# oresat-backplane-for-0_3.net
KiCad netlist of a schematic drawn in EAGLE
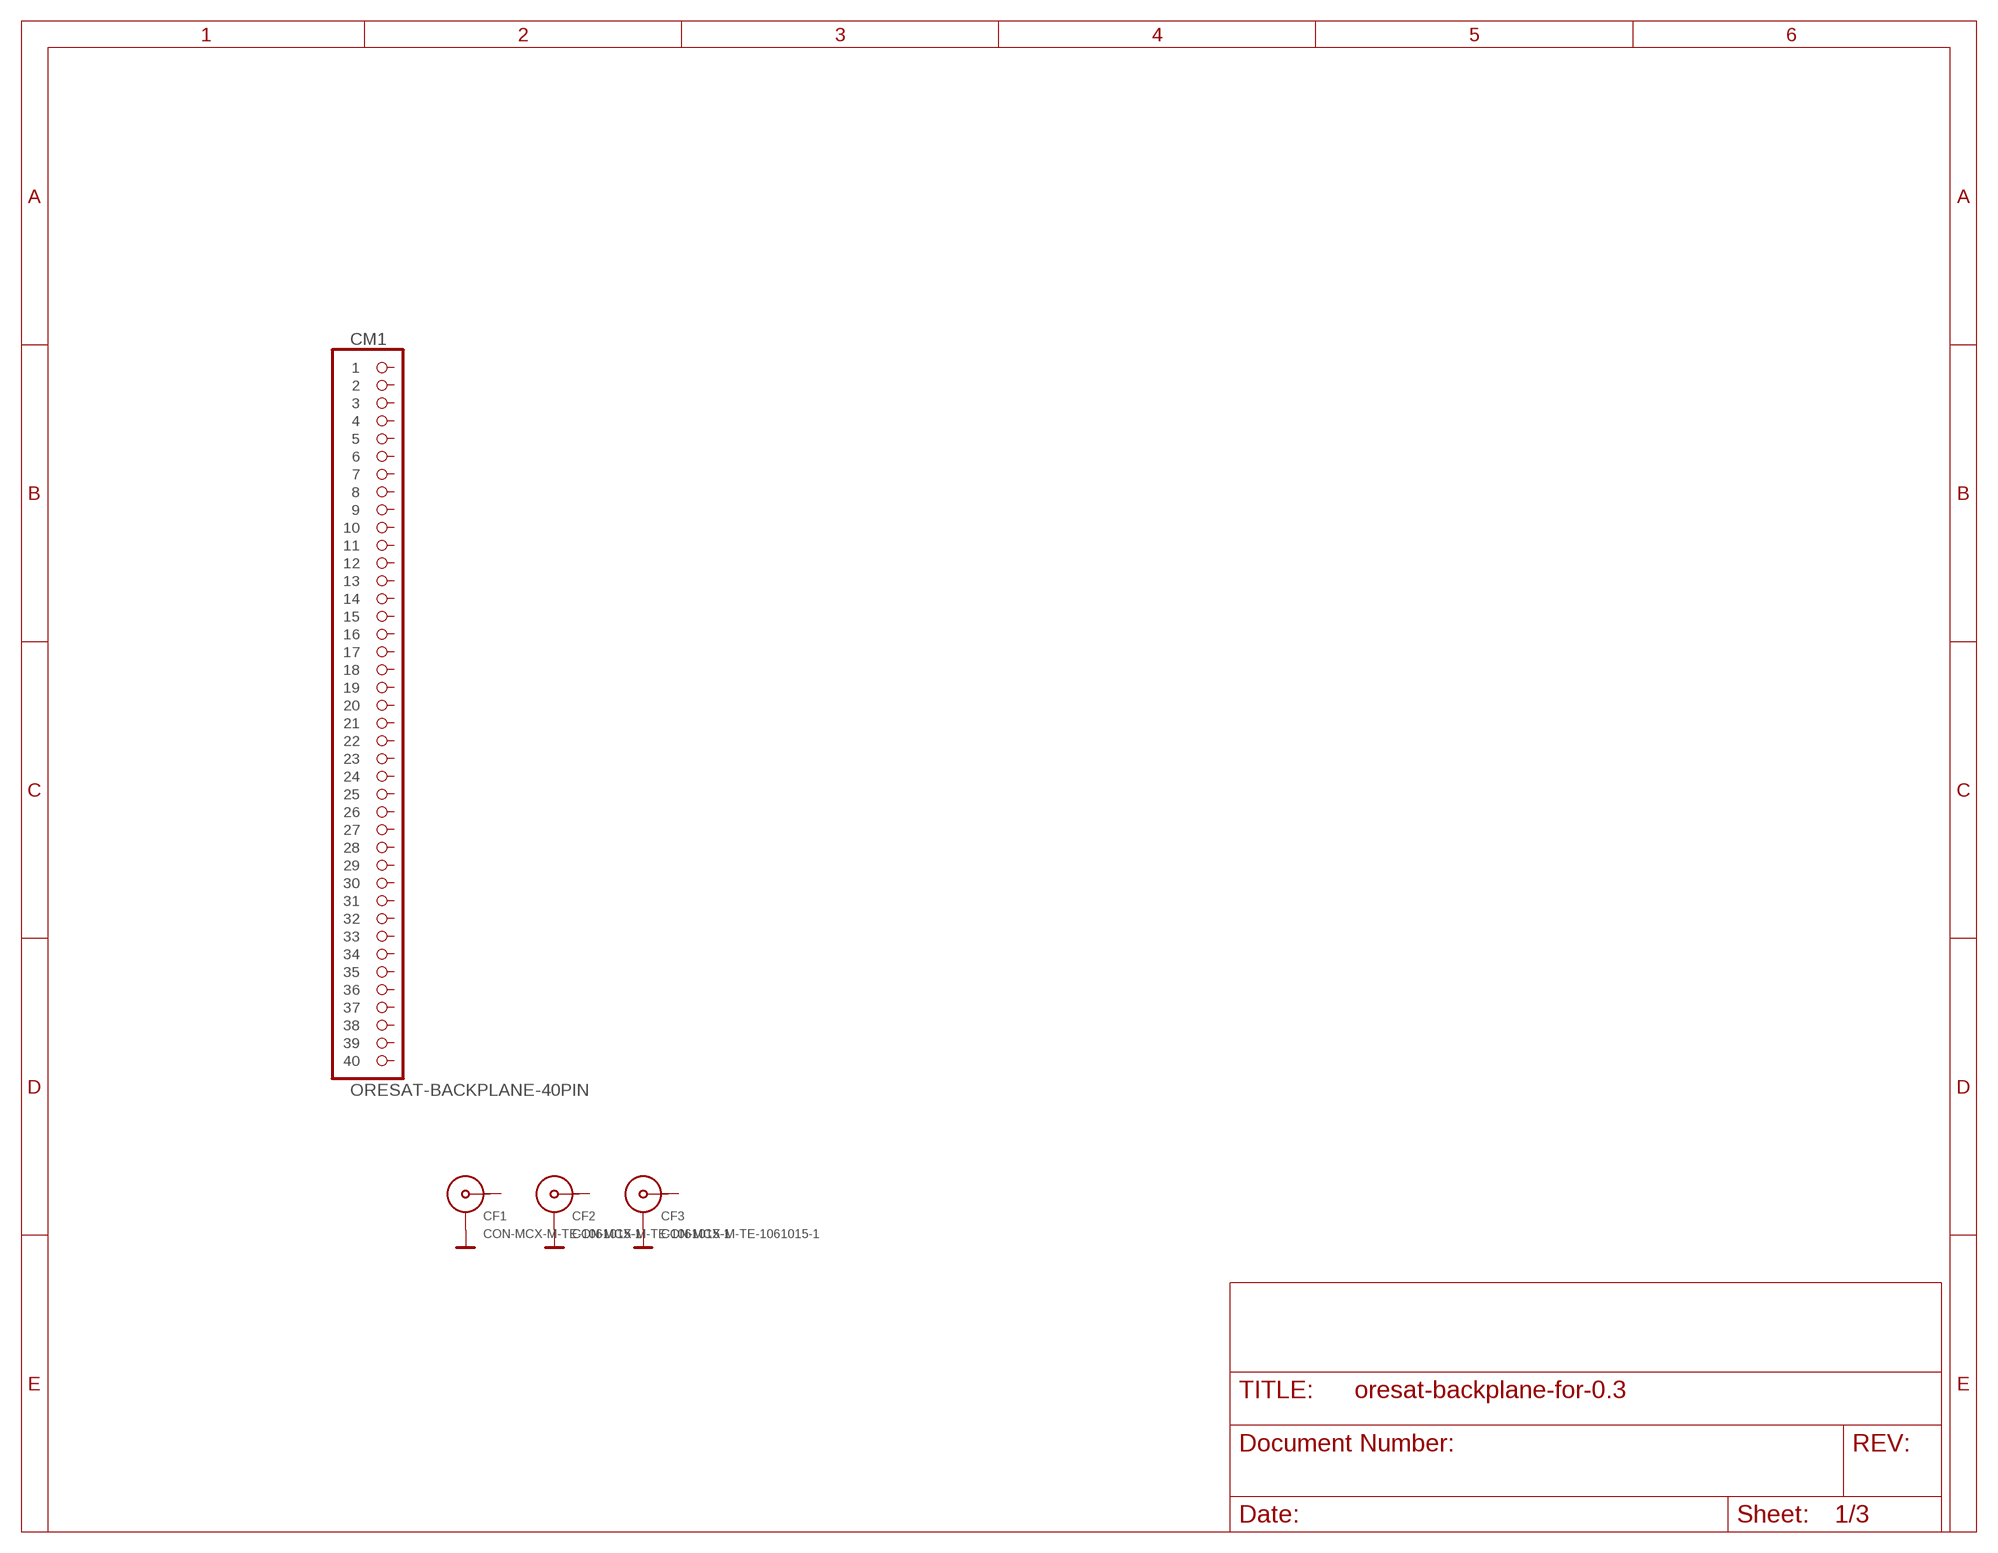
[diagram p0: schematic, sheet 1]
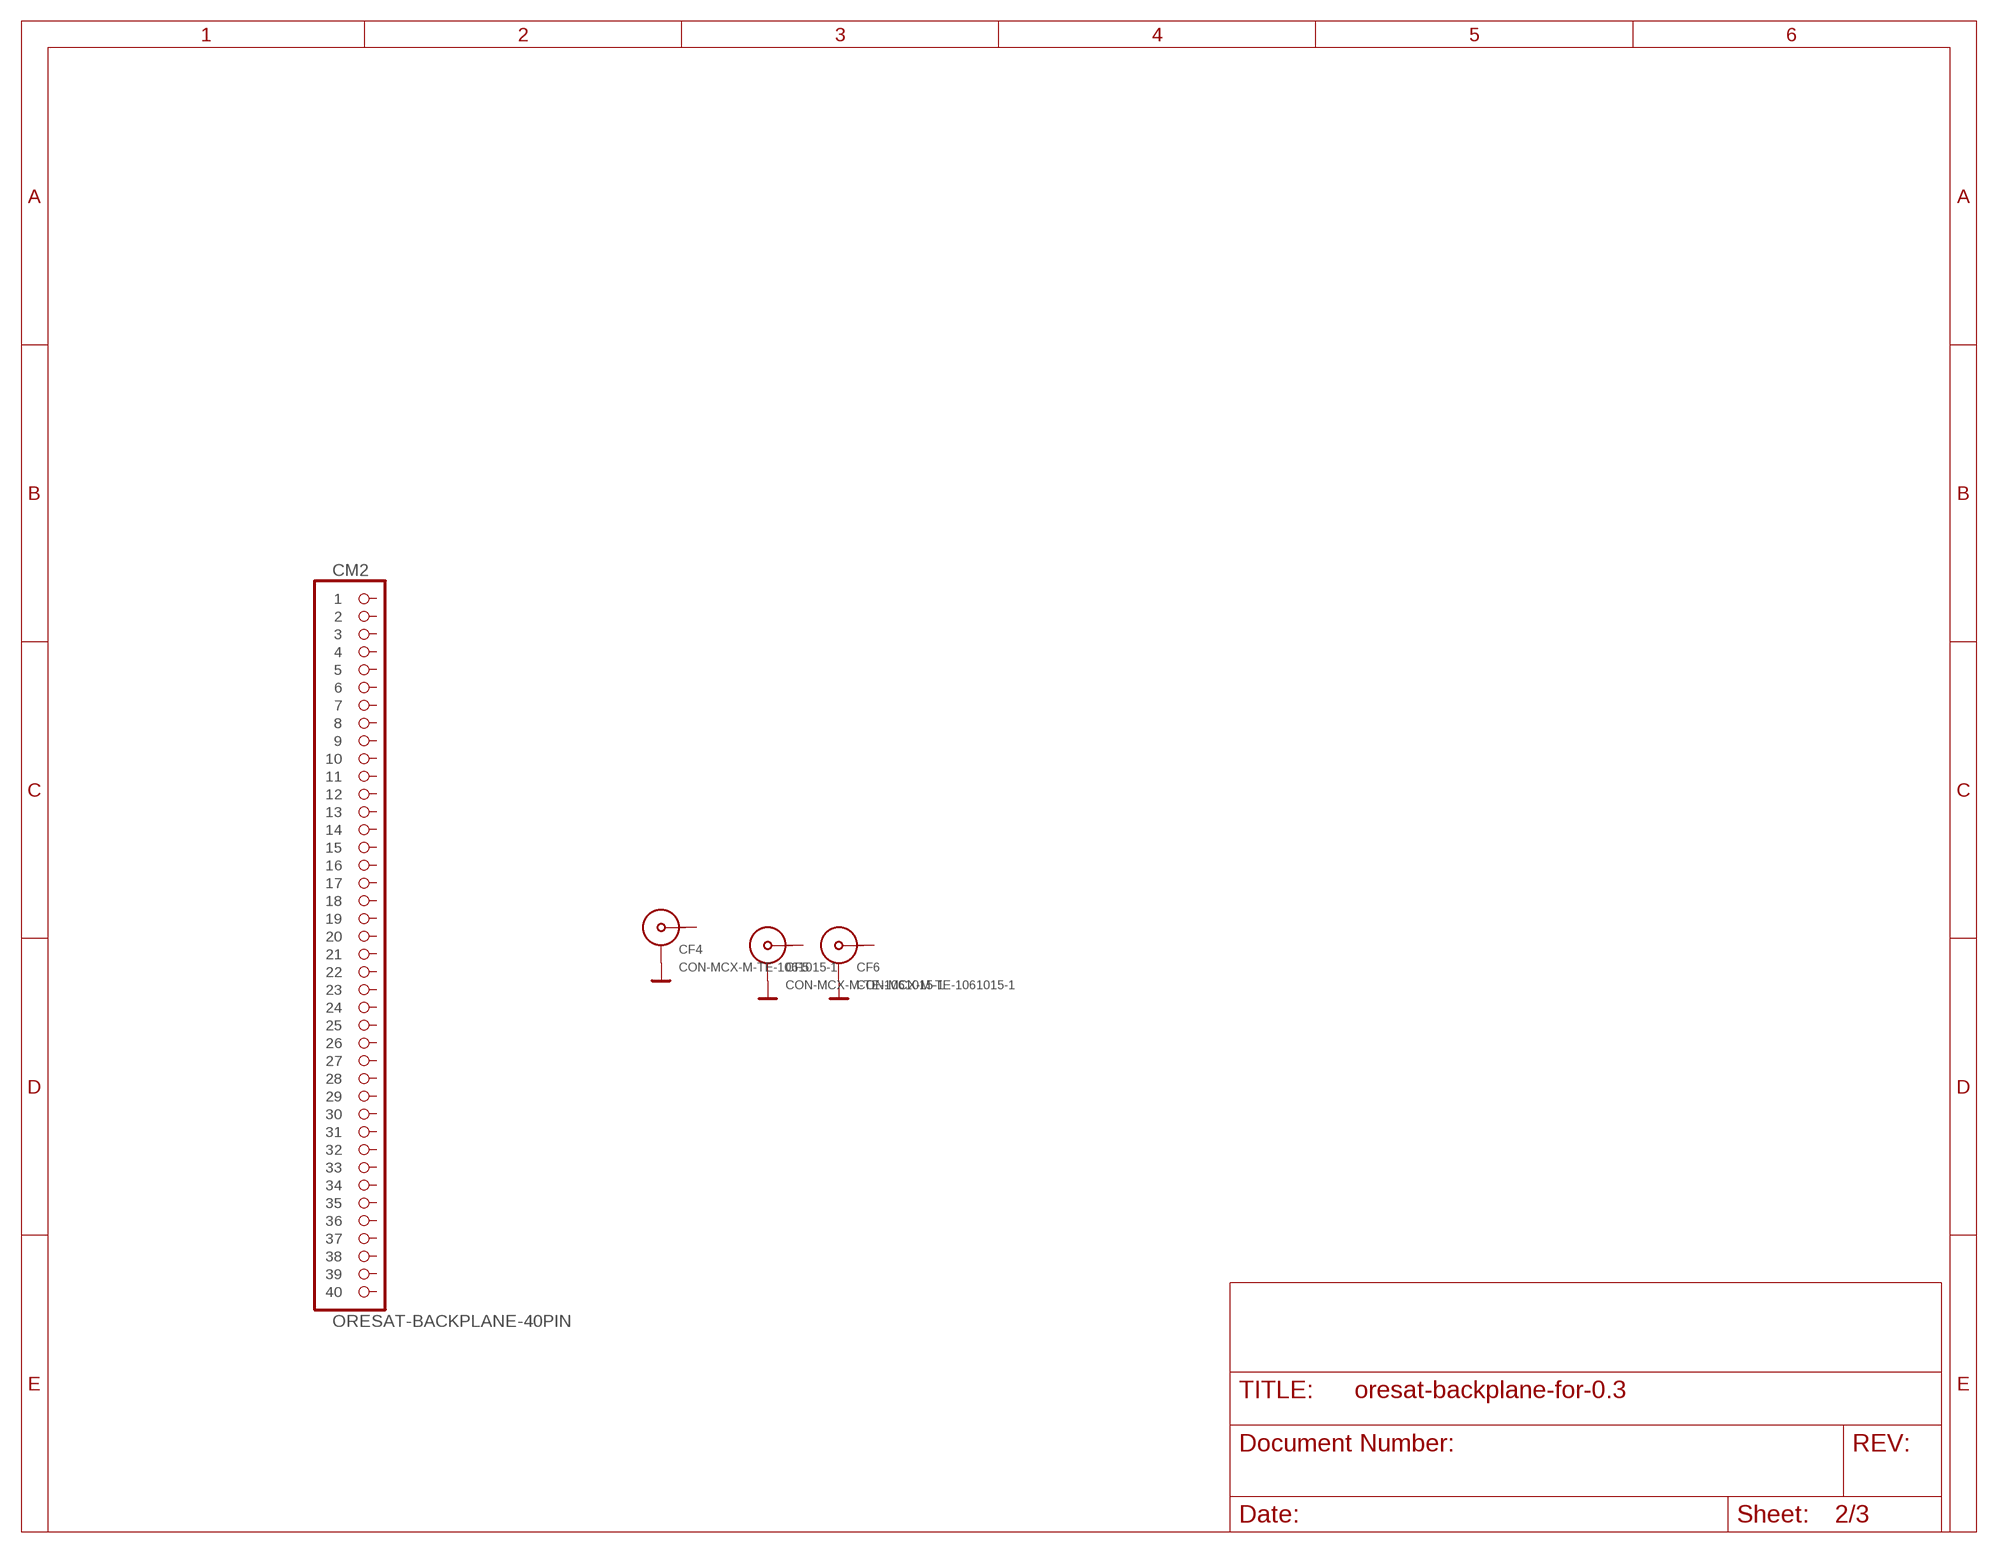
[diagram p1: schematic, sheet 2]
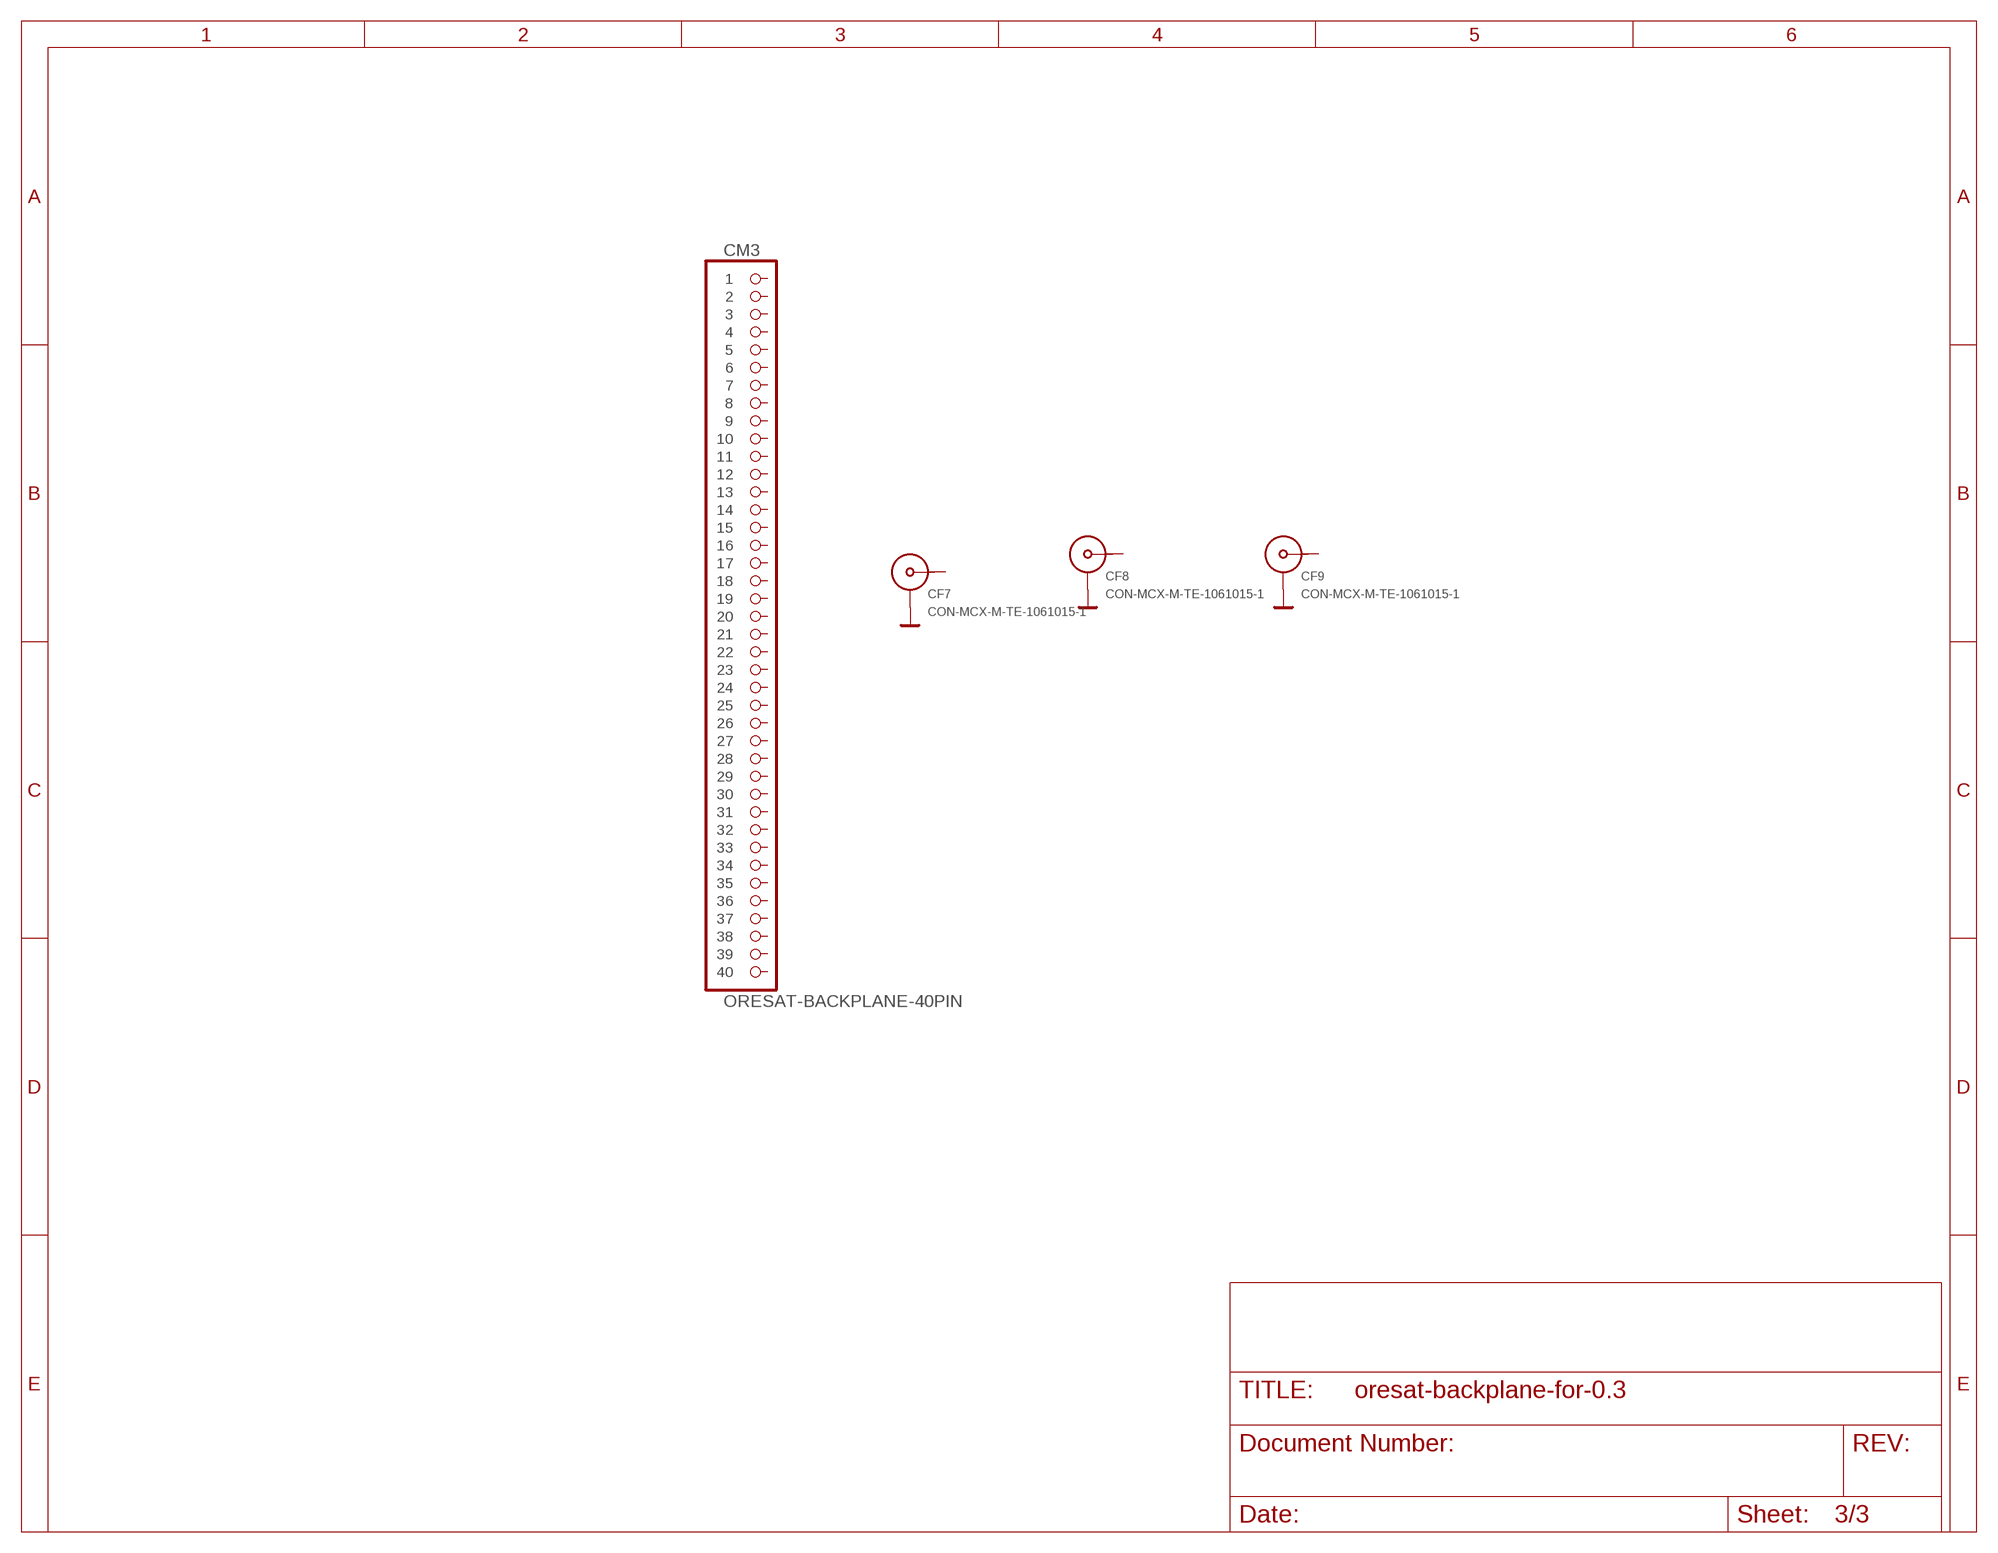
[diagram p2: schematic, sheet 3]

(export (version "E")
  (design (tool "Eeschema 10.0.6"))
  (components
    (comp (ref "CF4")
      (value "CON-MCX-M-TE-1061015-1")
      (footprint "eagle-import:CONN_1061015-1_TYCO")
      (fields
        (field (name "MANUFACTURER_PART_NUMBER") "1061015-1")
        (field (name "RSPARTNUMBER") "7130953")
        (field (name "COPYRIGHT") "Copyright (C) 2015 Accelerated Designs. All rights reserved")
      )
      (libsource (lib "eagle-import") (part "CON-MCX-M-TE-1061015-1"))
    )
    (comp (ref "CF5")
      (value "CON-MCX-M-TE-1061015-1")
      (footprint "eagle-import:CONN_1061015-1_TYCO")
      (fields
        (field (name "MANUFACTURER_PART_NUMBER") "1061015-1")
        (field (name "RSPARTNUMBER") "7130953")
        (field (name "COPYRIGHT") "Copyright (C) 2015 Accelerated Designs. All rights reserved")
      )
      (libsource (lib "eagle-import") (part "CON-MCX-M-TE-1061015-1"))
    )
    (comp (ref "CF6")
      (value "CON-MCX-M-TE-1061015-1")
      (footprint "eagle-import:CONN_1061015-1_TYCO")
      (fields
        (field (name "MANUFACTURER_PART_NUMBER") "1061015-1")
        (field (name "RSPARTNUMBER") "7130953")
        (field (name "COPYRIGHT") "Copyright (C) 2015 Accelerated Designs. All rights reserved")
      )
      (libsource (lib "eagle-import") (part "CON-MCX-M-TE-1061015-1"))
    )
    (comp (ref "CM2")
      (value "ORESAT-BACKPLANE-40PIN")
      (footprint "eagle-import:HARWIN-ARCHER-M50-3502042")
      (libsource (lib "eagle-import") (part "ORESAT-BACKPLANE-40PIN"))
    )
    (comp (ref "CF7")
      (value "CON-MCX-M-TE-1061015-1")
      (footprint "eagle-import:CONN_1061015-1_TYCO")
      (fields
        (field (name "MANUFACTURER_PART_NUMBER") "1061015-1")
        (field (name "RSPARTNUMBER") "7130953")
        (field (name "COPYRIGHT") "Copyright (C) 2015 Accelerated Designs. All rights reserved")
      )
      (libsource (lib "eagle-import") (part "CON-MCX-M-TE-1061015-1"))
    )
    (comp (ref "CF8")
      (value "CON-MCX-M-TE-1061015-1")
      (footprint "eagle-import:CONN_1061015-1_TYCO")
      (fields
        (field (name "MANUFACTURER_PART_NUMBER") "1061015-1")
        (field (name "RSPARTNUMBER") "7130953")
        (field (name "COPYRIGHT") "Copyright (C) 2015 Accelerated Designs. All rights reserved")
      )
      (libsource (lib "eagle-import") (part "CON-MCX-M-TE-1061015-1"))
    )
    (comp (ref "CF9")
      (value "CON-MCX-M-TE-1061015-1")
      (footprint "eagle-import:CONN_1061015-1_TYCO")
      (fields
        (field (name "MANUFACTURER_PART_NUMBER") "1061015-1")
        (field (name "RSPARTNUMBER") "7130953")
        (field (name "COPYRIGHT") "Copyright (C) 2015 Accelerated Designs. All rights reserved")
      )
      (libsource (lib "eagle-import") (part "CON-MCX-M-TE-1061015-1"))
    )
    (comp (ref "CM3")
      (value "ORESAT-BACKPLANE-40PIN")
      (footprint "eagle-import:HARWIN-ARCHER-M50-3502042")
      (libsource (lib "eagle-import") (part "ORESAT-BACKPLANE-40PIN"))
    )
    (comp (ref "CF1")
      (value "CON-MCX-M-TE-1061015-1")
      (footprint "eagle-import:CONN_1061015-1_TYCO")
      (fields
        (field (name "MANUFACTURER_PART_NUMBER") "1061015-1")
        (field (name "RSPARTNUMBER") "7130953")
        (field (name "COPYRIGHT") "Copyright (C) 2015 Accelerated Designs. All rights reserved")
      )
      (libsource (lib "eagle-import") (part "CON-MCX-M-TE-1061015-1"))
    )
    (comp (ref "CF2")
      (value "CON-MCX-M-TE-1061015-1")
      (footprint "eagle-import:CONN_1061015-1_TYCO")
      (fields
        (field (name "MANUFACTURER_PART_NUMBER") "1061015-1")
        (field (name "RSPARTNUMBER") "7130953")
        (field (name "COPYRIGHT") "Copyright (C) 2015 Accelerated Designs. All rights reserved")
      )
      (libsource (lib "eagle-import") (part "CON-MCX-M-TE-1061015-1"))
    )
    (comp (ref "CF3")
      (value "CON-MCX-M-TE-1061015-1")
      (footprint "eagle-import:CONN_1061015-1_TYCO")
      (fields
        (field (name "MANUFACTURER_PART_NUMBER") "1061015-1")
        (field (name "RSPARTNUMBER") "7130953")
        (field (name "COPYRIGHT") "Copyright (C) 2015 Accelerated Designs. All rights reserved")
      )
      (libsource (lib "eagle-import") (part "CON-MCX-M-TE-1061015-1"))
    )
    (comp (ref "CM1")
      (value "ORESAT-BACKPLANE-40PIN")
      (footprint "eagle-import:HARWIN-ARCHER-M50-3502042")
      (libsource (lib "eagle-import") (part "ORESAT-BACKPLANE-40PIN"))
    )
  )
  (nets
    (net (code "1") (name "GND") (class "Default")
      (node (ref "CF1") (pin "SHIELD1") (pinfunction "SHIELD_SHIELD1") (pintype "passive"))
      (node (ref "CF1") (pin "SHIELD2") (pinfunction "SHIELD_SHIELD2") (pintype "passive"))
      (node (ref "CF1") (pin "SHIELD3") (pinfunction "SHIELD_SHIELD3") (pintype "passive"))
      (node (ref "CF1") (pin "SHIELD4") (pinfunction "SHIELD_SHIELD4") (pintype "passive"))
      (node (ref "CF2") (pin "SHIELD1") (pinfunction "SHIELD_SHIELD1") (pintype "passive"))
      (node (ref "CF2") (pin "SHIELD2") (pinfunction "SHIELD_SHIELD2") (pintype "passive"))
      (node (ref "CF2") (pin "SHIELD3") (pinfunction "SHIELD_SHIELD3") (pintype "passive"))
      (node (ref "CF2") (pin "SHIELD4") (pinfunction "SHIELD_SHIELD4") (pintype "passive"))
      (node (ref "CF3") (pin "SHIELD1") (pinfunction "SHIELD_SHIELD1") (pintype "passive"))
      (node (ref "CF3") (pin "SHIELD2") (pinfunction "SHIELD_SHIELD2") (pintype "passive"))
      (node (ref "CF3") (pin "SHIELD3") (pinfunction "SHIELD_SHIELD3") (pintype "passive"))
      (node (ref "CF3") (pin "SHIELD4") (pinfunction "SHIELD_SHIELD4") (pintype "passive"))
      (node (ref "CF4") (pin "SHIELD1") (pinfunction "SHIELD_SHIELD1") (pintype "passive"))
      (node (ref "CF4") (pin "SHIELD2") (pinfunction "SHIELD_SHIELD2") (pintype "passive"))
      (node (ref "CF4") (pin "SHIELD3") (pinfunction "SHIELD_SHIELD3") (pintype "passive"))
      (node (ref "CF4") (pin "SHIELD4") (pinfunction "SHIELD_SHIELD4") (pintype "passive"))
      (node (ref "CF5") (pin "SHIELD1") (pinfunction "SHIELD_SHIELD1") (pintype "passive"))
      (node (ref "CF5") (pin "SHIELD2") (pinfunction "SHIELD_SHIELD2") (pintype "passive"))
      (node (ref "CF5") (pin "SHIELD3") (pinfunction "SHIELD_SHIELD3") (pintype "passive"))
      (node (ref "CF5") (pin "SHIELD4") (pinfunction "SHIELD_SHIELD4") (pintype "passive"))
      (node (ref "CF6") (pin "SHIELD1") (pinfunction "SHIELD_SHIELD1") (pintype "passive"))
      (node (ref "CF6") (pin "SHIELD2") (pinfunction "SHIELD_SHIELD2") (pintype "passive"))
      (node (ref "CF6") (pin "SHIELD3") (pinfunction "SHIELD_SHIELD3") (pintype "passive"))
      (node (ref "CF6") (pin "SHIELD4") (pinfunction "SHIELD_SHIELD4") (pintype "passive"))
      (node (ref "CF7") (pin "SHIELD1") (pinfunction "SHIELD_SHIELD1") (pintype "passive"))
      (node (ref "CF7") (pin "SHIELD2") (pinfunction "SHIELD_SHIELD2") (pintype "passive"))
      (node (ref "CF7") (pin "SHIELD3") (pinfunction "SHIELD_SHIELD3") (pintype "passive"))
      (node (ref "CF7") (pin "SHIELD4") (pinfunction "SHIELD_SHIELD4") (pintype "passive"))
      (node (ref "CF8") (pin "SHIELD1") (pinfunction "SHIELD_SHIELD1") (pintype "passive"))
      (node (ref "CF8") (pin "SHIELD2") (pinfunction "SHIELD_SHIELD2") (pintype "passive"))
      (node (ref "CF8") (pin "SHIELD3") (pinfunction "SHIELD_SHIELD3") (pintype "passive"))
      (node (ref "CF8") (pin "SHIELD4") (pinfunction "SHIELD_SHIELD4") (pintype "passive"))
      (node (ref "CF9") (pin "SHIELD1") (pinfunction "SHIELD_SHIELD1") (pintype "passive"))
      (node (ref "CF9") (pin "SHIELD2") (pinfunction "SHIELD_SHIELD2") (pintype "passive"))
      (node (ref "CF9") (pin "SHIELD3") (pinfunction "SHIELD_SHIELD3") (pintype "passive"))
      (node (ref "CF9") (pin "SHIELD4") (pinfunction "SHIELD_SHIELD4") (pintype "passive"))
    )
    (net (code "2") (name "unconnected-(CF1-PadCENTER)") (class "Default")
      (node (ref "CF1") (pin "CENTER") (pinfunction "CENTER_CENTER") (pintype "passive"))
    )
    (net (code "3") (name "unconnected-(CF2-PadCENTER)") (class "Default")
      (node (ref "CF2") (pin "CENTER") (pinfunction "CENTER_CENTER") (pintype "passive"))
    )
    (net (code "4") (name "unconnected-(CF3-PadCENTER)") (class "Default")
      (node (ref "CF3") (pin "CENTER") (pinfunction "CENTER_CENTER") (pintype "passive"))
    )
    (net (code "5") (name "unconnected-(CF4-PadCENTER)") (class "Default")
      (node (ref "CF4") (pin "CENTER") (pinfunction "CENTER_CENTER") (pintype "passive"))
    )
    (net (code "6") (name "unconnected-(CF5-PadCENTER)") (class "Default")
      (node (ref "CF5") (pin "CENTER") (pinfunction "CENTER_CENTER") (pintype "passive"))
    )
    (net (code "7") (name "unconnected-(CF6-PadCENTER)") (class "Default")
      (node (ref "CF6") (pin "CENTER") (pinfunction "CENTER_CENTER") (pintype "passive"))
    )
    (net (code "8") (name "unconnected-(CF7-PadCENTER)") (class "Default")
      (node (ref "CF7") (pin "CENTER") (pinfunction "CENTER_CENTER") (pintype "passive"))
    )
    (net (code "9") (name "unconnected-(CF8-PadCENTER)") (class "Default")
      (node (ref "CF8") (pin "CENTER") (pinfunction "CENTER_CENTER") (pintype "passive"))
    )
    (net (code "10") (name "unconnected-(CF9-PadCENTER)") (class "Default")
      (node (ref "CF9") (pin "CENTER") (pinfunction "CENTER_CENTER") (pintype "passive"))
    )
    (net (code "11") (name "unconnected-(CM1-1-PadP$1)") (class "Default")
      (node (ref "CM1") (pin "P$1") (pinfunction "1_P$1") (pintype "passive"))
    )
    (net (code "12") (name "unconnected-(CM1-2-PadP$2)") (class "Default")
      (node (ref "CM1") (pin "P$2") (pinfunction "2_P$2") (pintype "passive"))
    )
    (net (code "13") (name "unconnected-(CM1-3-PadP$3)") (class "Default")
      (node (ref "CM1") (pin "P$3") (pinfunction "3_P$3") (pintype "passive"))
    )
    (net (code "14") (name "unconnected-(CM1-4-PadP$4)") (class "Default")
      (node (ref "CM1") (pin "P$4") (pinfunction "4_P$4") (pintype "passive"))
    )
    (net (code "15") (name "unconnected-(CM1-5-PadP$5)") (class "Default")
      (node (ref "CM1") (pin "P$5") (pinfunction "5_P$5") (pintype "passive"))
    )
    (net (code "16") (name "unconnected-(CM1-6-PadP$6)") (class "Default")
      (node (ref "CM1") (pin "P$6") (pinfunction "6_P$6") (pintype "passive"))
    )
    (net (code "17") (name "unconnected-(CM1-7-PadP$7)") (class "Default")
      (node (ref "CM1") (pin "P$7") (pinfunction "7_P$7") (pintype "passive"))
    )
    (net (code "18") (name "unconnected-(CM1-8-PadP$8)") (class "Default")
      (node (ref "CM1") (pin "P$8") (pinfunction "8_P$8") (pintype "passive"))
    )
    (net (code "19") (name "unconnected-(CM1-9-PadP$9)") (class "Default")
      (node (ref "CM1") (pin "P$9") (pinfunction "9_P$9") (pintype "passive"))
    )
    (net (code "20") (name "unconnected-(CM1-10-PadP$10)") (class "Default")
      (node (ref "CM1") (pin "P$10") (pinfunction "10_P$10") (pintype "passive"))
    )
    (net (code "21") (name "unconnected-(CM1-11-PadP$11)") (class "Default")
      (node (ref "CM1") (pin "P$11") (pinfunction "11_P$11") (pintype "passive"))
    )
    (net (code "22") (name "unconnected-(CM1-12-PadP$12)") (class "Default")
      (node (ref "CM1") (pin "P$12") (pinfunction "12_P$12") (pintype "passive"))
    )
    (net (code "23") (name "unconnected-(CM1-13-PadP$13)") (class "Default")
      (node (ref "CM1") (pin "P$13") (pinfunction "13_P$13") (pintype "passive"))
    )
    (net (code "24") (name "unconnected-(CM1-14-PadP$14)") (class "Default")
      (node (ref "CM1") (pin "P$14") (pinfunction "14_P$14") (pintype "passive"))
    )
    (net (code "25") (name "unconnected-(CM1-15-PadP$15)") (class "Default")
      (node (ref "CM1") (pin "P$15") (pinfunction "15_P$15") (pintype "passive"))
    )
    (net (code "26") (name "unconnected-(CM1-16-PadP$16)") (class "Default")
      (node (ref "CM1") (pin "P$16") (pinfunction "16_P$16") (pintype "passive"))
    )
    (net (code "27") (name "unconnected-(CM1-17-PadP$17)") (class "Default")
      (node (ref "CM1") (pin "P$17") (pinfunction "17_P$17") (pintype "passive"))
    )
    (net (code "28") (name "unconnected-(CM1-18-PadP$18)") (class "Default")
      (node (ref "CM1") (pin "P$18") (pinfunction "18_P$18") (pintype "passive"))
    )
    (net (code "29") (name "unconnected-(CM1-19-PadP$19)") (class "Default")
      (node (ref "CM1") (pin "P$19") (pinfunction "19_P$19") (pintype "passive"))
    )
    (net (code "30") (name "unconnected-(CM1-20-PadP$20)") (class "Default")
      (node (ref "CM1") (pin "P$20") (pinfunction "20_P$20") (pintype "passive"))
    )
    (net (code "31") (name "unconnected-(CM1-21-PadP$21)") (class "Default")
      (node (ref "CM1") (pin "P$21") (pinfunction "21_P$21") (pintype "passive"))
    )
    (net (code "32") (name "unconnected-(CM1-22-PadP$22)") (class "Default")
      (node (ref "CM1") (pin "P$22") (pinfunction "22_P$22") (pintype "passive"))
    )
    (net (code "33") (name "unconnected-(CM1-23-PadP$23)") (class "Default")
      (node (ref "CM1") (pin "P$23") (pinfunction "23_P$23") (pintype "passive"))
    )
    (net (code "34") (name "unconnected-(CM1-24-PadP$24)") (class "Default")
      (node (ref "CM1") (pin "P$24") (pinfunction "24_P$24") (pintype "passive"))
    )
    (net (code "35") (name "unconnected-(CM1-25-PadP$25)") (class "Default")
      (node (ref "CM1") (pin "P$25") (pinfunction "25_P$25") (pintype "passive"))
    )
    (net (code "36") (name "unconnected-(CM1-26-PadP$26)") (class "Default")
      (node (ref "CM1") (pin "P$26") (pinfunction "26_P$26") (pintype "passive"))
    )
    (net (code "37") (name "unconnected-(CM1-27-PadP$27)") (class "Default")
      (node (ref "CM1") (pin "P$27") (pinfunction "27_P$27") (pintype "passive"))
    )
    (net (code "38") (name "unconnected-(CM1-28-PadP$28)") (class "Default")
      (node (ref "CM1") (pin "P$28") (pinfunction "28_P$28") (pintype "passive"))
    )
    (net (code "39") (name "unconnected-(CM1-29-PadP$29)") (class "Default")
      (node (ref "CM1") (pin "P$29") (pinfunction "29_P$29") (pintype "passive"))
    )
    (net (code "40") (name "unconnected-(CM1-30-PadP$30)") (class "Default")
      (node (ref "CM1") (pin "P$30") (pinfunction "30_P$30") (pintype "passive"))
    )
    (net (code "41") (name "unconnected-(CM1-31-PadP$31)") (class "Default")
      (node (ref "CM1") (pin "P$31") (pinfunction "31_P$31") (pintype "passive"))
    )
    (net (code "42") (name "unconnected-(CM1-32-PadP$32)") (class "Default")
      (node (ref "CM1") (pin "P$32") (pinfunction "32_P$32") (pintype "passive"))
    )
    (net (code "43") (name "unconnected-(CM1-33-PadP$33)") (class "Default")
      (node (ref "CM1") (pin "P$33") (pinfunction "33_P$33") (pintype "passive"))
    )
    (net (code "44") (name "unconnected-(CM1-34-PadP$34)") (class "Default")
      (node (ref "CM1") (pin "P$34") (pinfunction "34_P$34") (pintype "passive"))
    )
    (net (code "45") (name "unconnected-(CM1-35-PadP$35)") (class "Default")
      (node (ref "CM1") (pin "P$35") (pinfunction "35_P$35") (pintype "passive"))
    )
    (net (code "46") (name "unconnected-(CM1-36-PadP$36)") (class "Default")
      (node (ref "CM1") (pin "P$36") (pinfunction "36_P$36") (pintype "passive"))
    )
    (net (code "47") (name "unconnected-(CM1-37-PadP$37)") (class "Default")
      (node (ref "CM1") (pin "P$37") (pinfunction "37_P$37") (pintype "passive"))
    )
    (net (code "48") (name "unconnected-(CM1-38-PadP$38)") (class "Default")
      (node (ref "CM1") (pin "P$38") (pinfunction "38_P$38") (pintype "passive"))
    )
    (net (code "49") (name "unconnected-(CM1-39-PadP$39)") (class "Default")
      (node (ref "CM1") (pin "P$39") (pinfunction "39_P$39") (pintype "passive"))
    )
    (net (code "50") (name "unconnected-(CM1-40-PadP$40)") (class "Default")
      (node (ref "CM1") (pin "P$40") (pinfunction "40_P$40") (pintype "passive"))
    )
    (net (code "51") (name "unconnected-(CM2-1-PadP$1)") (class "Default")
      (node (ref "CM2") (pin "P$1") (pinfunction "1_P$1") (pintype "passive"))
    )
    (net (code "52") (name "unconnected-(CM2-2-PadP$2)") (class "Default")
      (node (ref "CM2") (pin "P$2") (pinfunction "2_P$2") (pintype "passive"))
    )
    (net (code "53") (name "unconnected-(CM2-3-PadP$3)") (class "Default")
      (node (ref "CM2") (pin "P$3") (pinfunction "3_P$3") (pintype "passive"))
    )
    (net (code "54") (name "unconnected-(CM2-4-PadP$4)") (class "Default")
      (node (ref "CM2") (pin "P$4") (pinfunction "4_P$4") (pintype "passive"))
    )
    (net (code "55") (name "unconnected-(CM2-5-PadP$5)") (class "Default")
      (node (ref "CM2") (pin "P$5") (pinfunction "5_P$5") (pintype "passive"))
    )
    (net (code "56") (name "unconnected-(CM2-6-PadP$6)") (class "Default")
      (node (ref "CM2") (pin "P$6") (pinfunction "6_P$6") (pintype "passive"))
    )
    (net (code "57") (name "unconnected-(CM2-7-PadP$7)") (class "Default")
      (node (ref "CM2") (pin "P$7") (pinfunction "7_P$7") (pintype "passive"))
    )
    (net (code "58") (name "unconnected-(CM2-8-PadP$8)") (class "Default")
      (node (ref "CM2") (pin "P$8") (pinfunction "8_P$8") (pintype "passive"))
    )
    (net (code "59") (name "unconnected-(CM2-9-PadP$9)") (class "Default")
      (node (ref "CM2") (pin "P$9") (pinfunction "9_P$9") (pintype "passive"))
    )
    (net (code "60") (name "unconnected-(CM2-10-PadP$10)") (class "Default")
      (node (ref "CM2") (pin "P$10") (pinfunction "10_P$10") (pintype "passive"))
    )
    (net (code "61") (name "unconnected-(CM2-11-PadP$11)") (class "Default")
      (node (ref "CM2") (pin "P$11") (pinfunction "11_P$11") (pintype "passive"))
    )
    (net (code "62") (name "unconnected-(CM2-12-PadP$12)") (class "Default")
      (node (ref "CM2") (pin "P$12") (pinfunction "12_P$12") (pintype "passive"))
    )
    (net (code "63") (name "unconnected-(CM2-13-PadP$13)") (class "Default")
      (node (ref "CM2") (pin "P$13") (pinfunction "13_P$13") (pintype "passive"))
    )
    (net (code "64") (name "unconnected-(CM2-14-PadP$14)") (class "Default")
      (node (ref "CM2") (pin "P$14") (pinfunction "14_P$14") (pintype "passive"))
    )
    (net (code "65") (name "unconnected-(CM2-15-PadP$15)") (class "Default")
      (node (ref "CM2") (pin "P$15") (pinfunction "15_P$15") (pintype "passive"))
    )
    (net (code "66") (name "unconnected-(CM2-16-PadP$16)") (class "Default")
      (node (ref "CM2") (pin "P$16") (pinfunction "16_P$16") (pintype "passive"))
    )
    (net (code "67") (name "unconnected-(CM2-17-PadP$17)") (class "Default")
      (node (ref "CM2") (pin "P$17") (pinfunction "17_P$17") (pintype "passive"))
    )
    (net (code "68") (name "unconnected-(CM2-18-PadP$18)") (class "Default")
      (node (ref "CM2") (pin "P$18") (pinfunction "18_P$18") (pintype "passive"))
    )
    (net (code "69") (name "unconnected-(CM2-19-PadP$19)") (class "Default")
      (node (ref "CM2") (pin "P$19") (pinfunction "19_P$19") (pintype "passive"))
    )
    (net (code "70") (name "unconnected-(CM2-20-PadP$20)") (class "Default")
      (node (ref "CM2") (pin "P$20") (pinfunction "20_P$20") (pintype "passive"))
    )
    (net (code "71") (name "unconnected-(CM2-21-PadP$21)") (class "Default")
      (node (ref "CM2") (pin "P$21") (pinfunction "21_P$21") (pintype "passive"))
    )
    (net (code "72") (name "unconnected-(CM2-22-PadP$22)") (class "Default")
      (node (ref "CM2") (pin "P$22") (pinfunction "22_P$22") (pintype "passive"))
    )
    (net (code "73") (name "unconnected-(CM2-23-PadP$23)") (class "Default")
      (node (ref "CM2") (pin "P$23") (pinfunction "23_P$23") (pintype "passive"))
    )
    (net (code "74") (name "unconnected-(CM2-24-PadP$24)") (class "Default")
      (node (ref "CM2") (pin "P$24") (pinfunction "24_P$24") (pintype "passive"))
    )
    (net (code "75") (name "unconnected-(CM2-25-PadP$25)") (class "Default")
      (node (ref "CM2") (pin "P$25") (pinfunction "25_P$25") (pintype "passive"))
    )
    (net (code "76") (name "unconnected-(CM2-26-PadP$26)") (class "Default")
      (node (ref "CM2") (pin "P$26") (pinfunction "26_P$26") (pintype "passive"))
    )
    (net (code "77") (name "unconnected-(CM2-27-PadP$27)") (class "Default")
      (node (ref "CM2") (pin "P$27") (pinfunction "27_P$27") (pintype "passive"))
    )
    (net (code "78") (name "unconnected-(CM2-28-PadP$28)") (class "Default")
      (node (ref "CM2") (pin "P$28") (pinfunction "28_P$28") (pintype "passive"))
    )
    (net (code "79") (name "unconnected-(CM2-29-PadP$29)") (class "Default")
      (node (ref "CM2") (pin "P$29") (pinfunction "29_P$29") (pintype "passive"))
    )
    (net (code "80") (name "unconnected-(CM2-30-PadP$30)") (class "Default")
      (node (ref "CM2") (pin "P$30") (pinfunction "30_P$30") (pintype "passive"))
    )
    (net (code "81") (name "unconnected-(CM2-31-PadP$31)") (class "Default")
      (node (ref "CM2") (pin "P$31") (pinfunction "31_P$31") (pintype "passive"))
    )
    (net (code "82") (name "unconnected-(CM2-32-PadP$32)") (class "Default")
      (node (ref "CM2") (pin "P$32") (pinfunction "32_P$32") (pintype "passive"))
    )
    (net (code "83") (name "unconnected-(CM2-33-PadP$33)") (class "Default")
      (node (ref "CM2") (pin "P$33") (pinfunction "33_P$33") (pintype "passive"))
    )
    (net (code "84") (name "unconnected-(CM2-34-PadP$34)") (class "Default")
      (node (ref "CM2") (pin "P$34") (pinfunction "34_P$34") (pintype "passive"))
    )
    (net (code "85") (name "unconnected-(CM2-35-PadP$35)") (class "Default")
      (node (ref "CM2") (pin "P$35") (pinfunction "35_P$35") (pintype "passive"))
    )
    (net (code "86") (name "unconnected-(CM2-36-PadP$36)") (class "Default")
      (node (ref "CM2") (pin "P$36") (pinfunction "36_P$36") (pintype "passive"))
    )
    (net (code "87") (name "unconnected-(CM2-37-PadP$37)") (class "Default")
      (node (ref "CM2") (pin "P$37") (pinfunction "37_P$37") (pintype "passive"))
    )
    (net (code "88") (name "unconnected-(CM2-38-PadP$38)") (class "Default")
      (node (ref "CM2") (pin "P$38") (pinfunction "38_P$38") (pintype "passive"))
    )
    (net (code "89") (name "unconnected-(CM2-39-PadP$39)") (class "Default")
      (node (ref "CM2") (pin "P$39") (pinfunction "39_P$39") (pintype "passive"))
    )
    (net (code "90") (name "unconnected-(CM2-40-PadP$40)") (class "Default")
      (node (ref "CM2") (pin "P$40") (pinfunction "40_P$40") (pintype "passive"))
    )
    (net (code "91") (name "unconnected-(CM3-1-PadP$1)") (class "Default")
      (node (ref "CM3") (pin "P$1") (pinfunction "1_P$1") (pintype "passive"))
    )
    (net (code "92") (name "unconnected-(CM3-2-PadP$2)") (class "Default")
      (node (ref "CM3") (pin "P$2") (pinfunction "2_P$2") (pintype "passive"))
    )
    (net (code "93") (name "unconnected-(CM3-3-PadP$3)") (class "Default")
      (node (ref "CM3") (pin "P$3") (pinfunction "3_P$3") (pintype "passive"))
    )
    (net (code "94") (name "unconnected-(CM3-4-PadP$4)") (class "Default")
      (node (ref "CM3") (pin "P$4") (pinfunction "4_P$4") (pintype "passive"))
    )
    (net (code "95") (name "unconnected-(CM3-5-PadP$5)") (class "Default")
      (node (ref "CM3") (pin "P$5") (pinfunction "5_P$5") (pintype "passive"))
    )
    (net (code "96") (name "unconnected-(CM3-6-PadP$6)") (class "Default")
      (node (ref "CM3") (pin "P$6") (pinfunction "6_P$6") (pintype "passive"))
    )
    (net (code "97") (name "unconnected-(CM3-7-PadP$7)") (class "Default")
      (node (ref "CM3") (pin "P$7") (pinfunction "7_P$7") (pintype "passive"))
    )
    (net (code "98") (name "unconnected-(CM3-8-PadP$8)") (class "Default")
      (node (ref "CM3") (pin "P$8") (pinfunction "8_P$8") (pintype "passive"))
    )
    (net (code "99") (name "unconnected-(CM3-9-PadP$9)") (class "Default")
      (node (ref "CM3") (pin "P$9") (pinfunction "9_P$9") (pintype "passive"))
    )
    (net (code "100") (name "unconnected-(CM3-10-PadP$10)") (class "Default")
      (node (ref "CM3") (pin "P$10") (pinfunction "10_P$10") (pintype "passive"))
    )
    (net (code "101") (name "unconnected-(CM3-11-PadP$11)") (class "Default")
      (node (ref "CM3") (pin "P$11") (pinfunction "11_P$11") (pintype "passive"))
    )
    (net (code "102") (name "unconnected-(CM3-12-PadP$12)") (class "Default")
      (node (ref "CM3") (pin "P$12") (pinfunction "12_P$12") (pintype "passive"))
    )
    (net (code "103") (name "unconnected-(CM3-13-PadP$13)") (class "Default")
      (node (ref "CM3") (pin "P$13") (pinfunction "13_P$13") (pintype "passive"))
    )
    (net (code "104") (name "unconnected-(CM3-14-PadP$14)") (class "Default")
      (node (ref "CM3") (pin "P$14") (pinfunction "14_P$14") (pintype "passive"))
    )
    (net (code "105") (name "unconnected-(CM3-15-PadP$15)") (class "Default")
      (node (ref "CM3") (pin "P$15") (pinfunction "15_P$15") (pintype "passive"))
    )
    (net (code "106") (name "unconnected-(CM3-16-PadP$16)") (class "Default")
      (node (ref "CM3") (pin "P$16") (pinfunction "16_P$16") (pintype "passive"))
    )
    (net (code "107") (name "unconnected-(CM3-17-PadP$17)") (class "Default")
      (node (ref "CM3") (pin "P$17") (pinfunction "17_P$17") (pintype "passive"))
    )
    (net (code "108") (name "unconnected-(CM3-18-PadP$18)") (class "Default")
      (node (ref "CM3") (pin "P$18") (pinfunction "18_P$18") (pintype "passive"))
    )
    (net (code "109") (name "unconnected-(CM3-19-PadP$19)") (class "Default")
      (node (ref "CM3") (pin "P$19") (pinfunction "19_P$19") (pintype "passive"))
    )
    (net (code "110") (name "unconnected-(CM3-20-PadP$20)") (class "Default")
      (node (ref "CM3") (pin "P$20") (pinfunction "20_P$20") (pintype "passive"))
    )
    (net (code "111") (name "unconnected-(CM3-21-PadP$21)") (class "Default")
      (node (ref "CM3") (pin "P$21") (pinfunction "21_P$21") (pintype "passive"))
    )
    (net (code "112") (name "unconnected-(CM3-22-PadP$22)") (class "Default")
      (node (ref "CM3") (pin "P$22") (pinfunction "22_P$22") (pintype "passive"))
    )
    (net (code "113") (name "unconnected-(CM3-23-PadP$23)") (class "Default")
      (node (ref "CM3") (pin "P$23") (pinfunction "23_P$23") (pintype "passive"))
    )
    (net (code "114") (name "unconnected-(CM3-24-PadP$24)") (class "Default")
      (node (ref "CM3") (pin "P$24") (pinfunction "24_P$24") (pintype "passive"))
    )
    (net (code "115") (name "unconnected-(CM3-25-PadP$25)") (class "Default")
      (node (ref "CM3") (pin "P$25") (pinfunction "25_P$25") (pintype "passive"))
    )
    (net (code "116") (name "unconnected-(CM3-26-PadP$26)") (class "Default")
      (node (ref "CM3") (pin "P$26") (pinfunction "26_P$26") (pintype "passive"))
    )
    (net (code "117") (name "unconnected-(CM3-27-PadP$27)") (class "Default")
      (node (ref "CM3") (pin "P$27") (pinfunction "27_P$27") (pintype "passive"))
    )
    (net (code "118") (name "unconnected-(CM3-28-PadP$28)") (class "Default")
      (node (ref "CM3") (pin "P$28") (pinfunction "28_P$28") (pintype "passive"))
    )
    (net (code "119") (name "unconnected-(CM3-29-PadP$29)") (class "Default")
      (node (ref "CM3") (pin "P$29") (pinfunction "29_P$29") (pintype "passive"))
    )
    (net (code "120") (name "unconnected-(CM3-30-PadP$30)") (class "Default")
      (node (ref "CM3") (pin "P$30") (pinfunction "30_P$30") (pintype "passive"))
    )
    (net (code "121") (name "unconnected-(CM3-31-PadP$31)") (class "Default")
      (node (ref "CM3") (pin "P$31") (pinfunction "31_P$31") (pintype "passive"))
    )
    (net (code "122") (name "unconnected-(CM3-32-PadP$32)") (class "Default")
      (node (ref "CM3") (pin "P$32") (pinfunction "32_P$32") (pintype "passive"))
    )
    (net (code "123") (name "unconnected-(CM3-33-PadP$33)") (class "Default")
      (node (ref "CM3") (pin "P$33") (pinfunction "33_P$33") (pintype "passive"))
    )
    (net (code "124") (name "unconnected-(CM3-34-PadP$34)") (class "Default")
      (node (ref "CM3") (pin "P$34") (pinfunction "34_P$34") (pintype "passive"))
    )
    (net (code "125") (name "unconnected-(CM3-35-PadP$35)") (class "Default")
      (node (ref "CM3") (pin "P$35") (pinfunction "35_P$35") (pintype "passive"))
    )
    (net (code "126") (name "unconnected-(CM3-36-PadP$36)") (class "Default")
      (node (ref "CM3") (pin "P$36") (pinfunction "36_P$36") (pintype "passive"))
    )
    (net (code "127") (name "unconnected-(CM3-37-PadP$37)") (class "Default")
      (node (ref "CM3") (pin "P$37") (pinfunction "37_P$37") (pintype "passive"))
    )
    (net (code "128") (name "unconnected-(CM3-38-PadP$38)") (class "Default")
      (node (ref "CM3") (pin "P$38") (pinfunction "38_P$38") (pintype "passive"))
    )
    (net (code "129") (name "unconnected-(CM3-39-PadP$39)") (class "Default")
      (node (ref "CM3") (pin "P$39") (pinfunction "39_P$39") (pintype "passive"))
    )
    (net (code "130") (name "unconnected-(CM3-40-PadP$40)") (class "Default")
      (node (ref "CM3") (pin "P$40") (pinfunction "40_P$40") (pintype "passive"))
    )
  )
)
